# nRF_touch.net
KiCad netlist of a schematic drawn in EAGLE
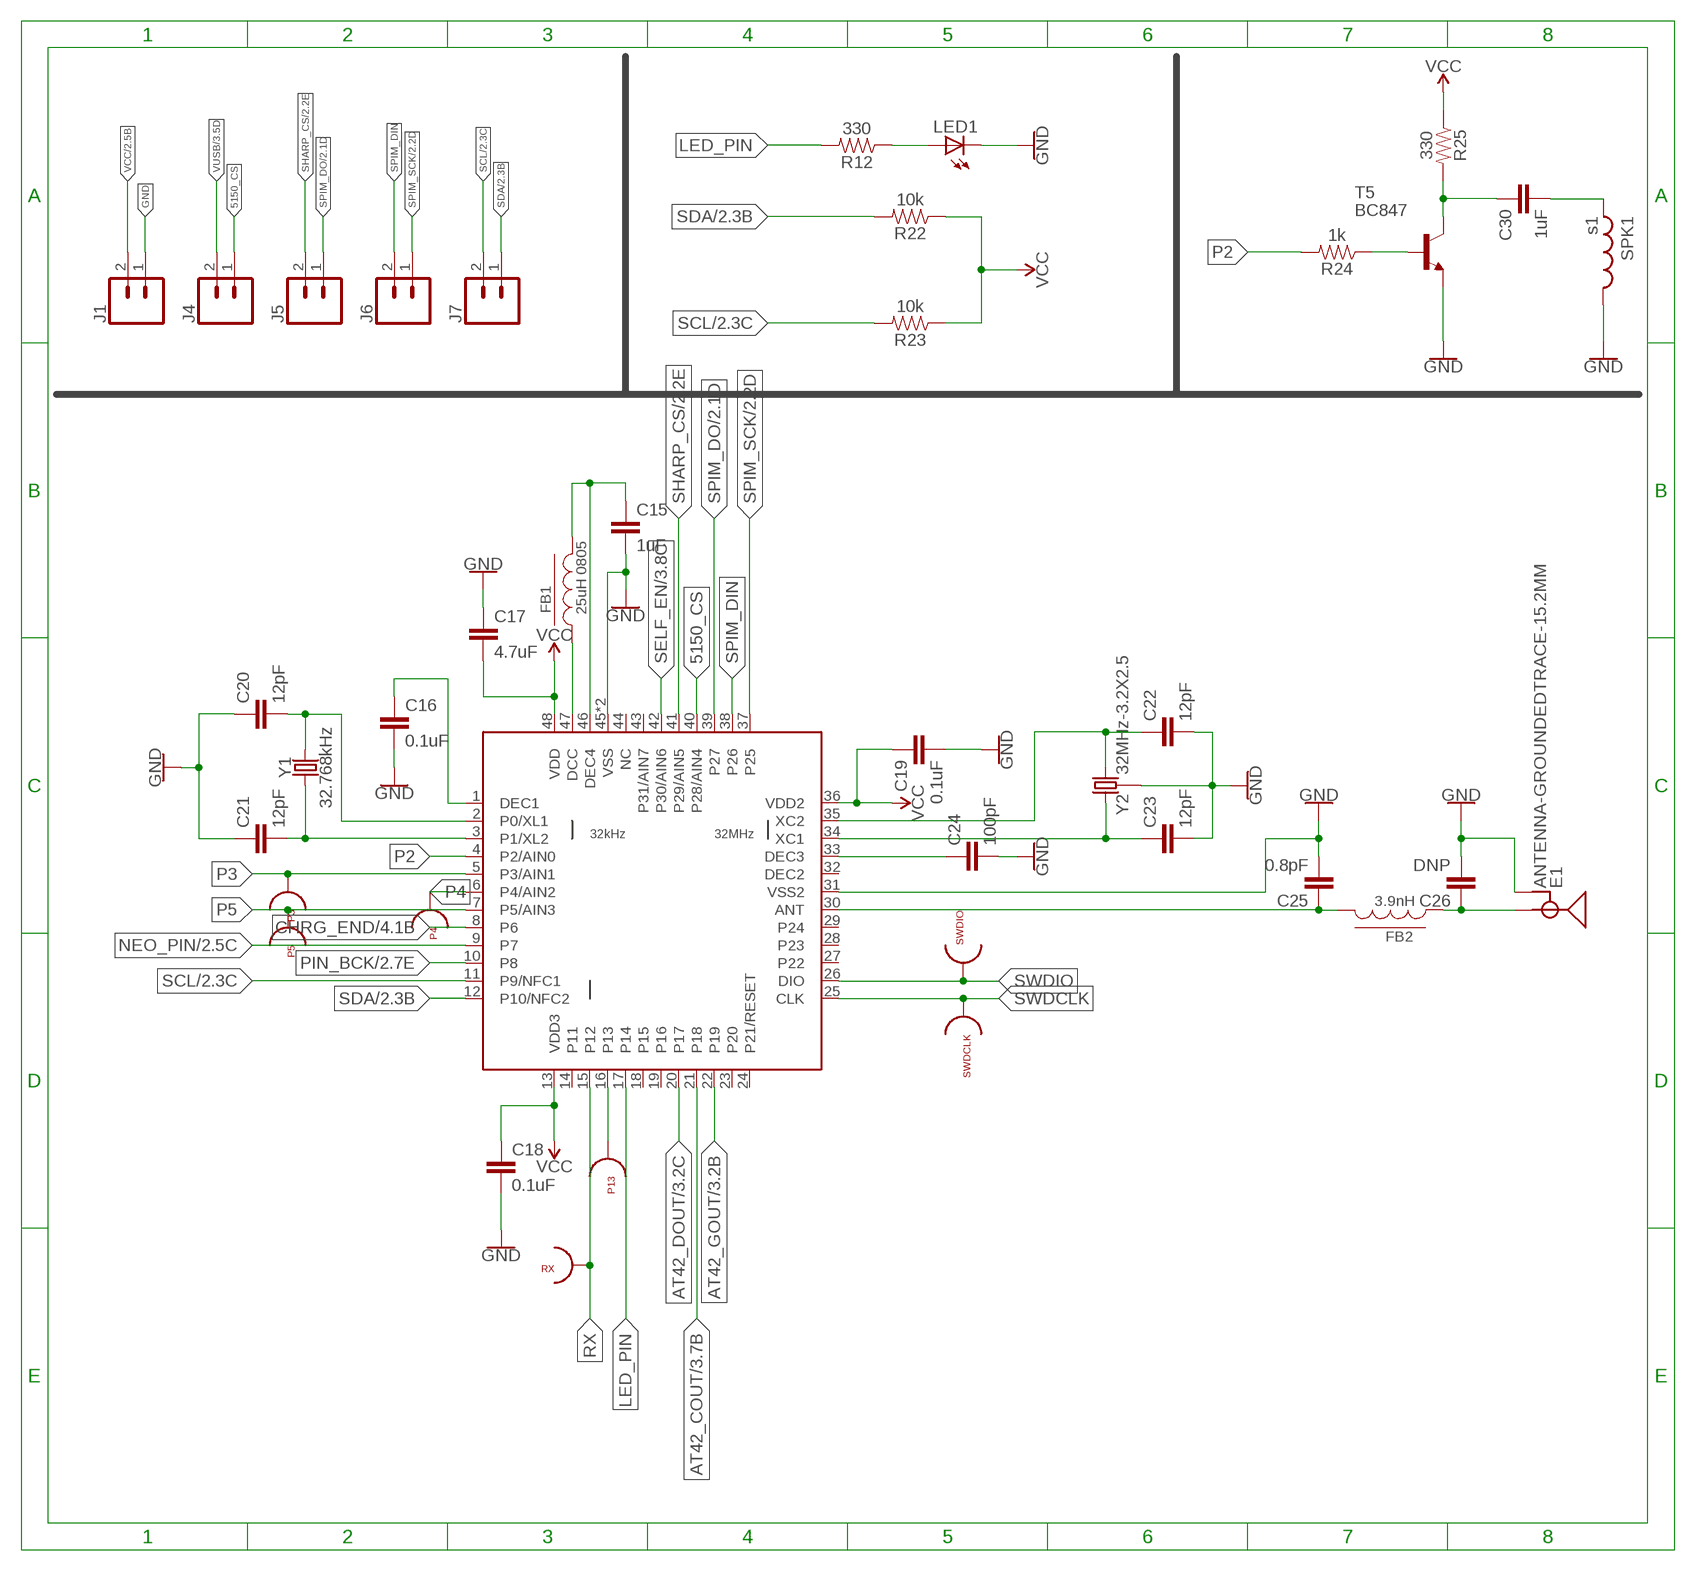
[diagram p0: schematic, sheet 1]
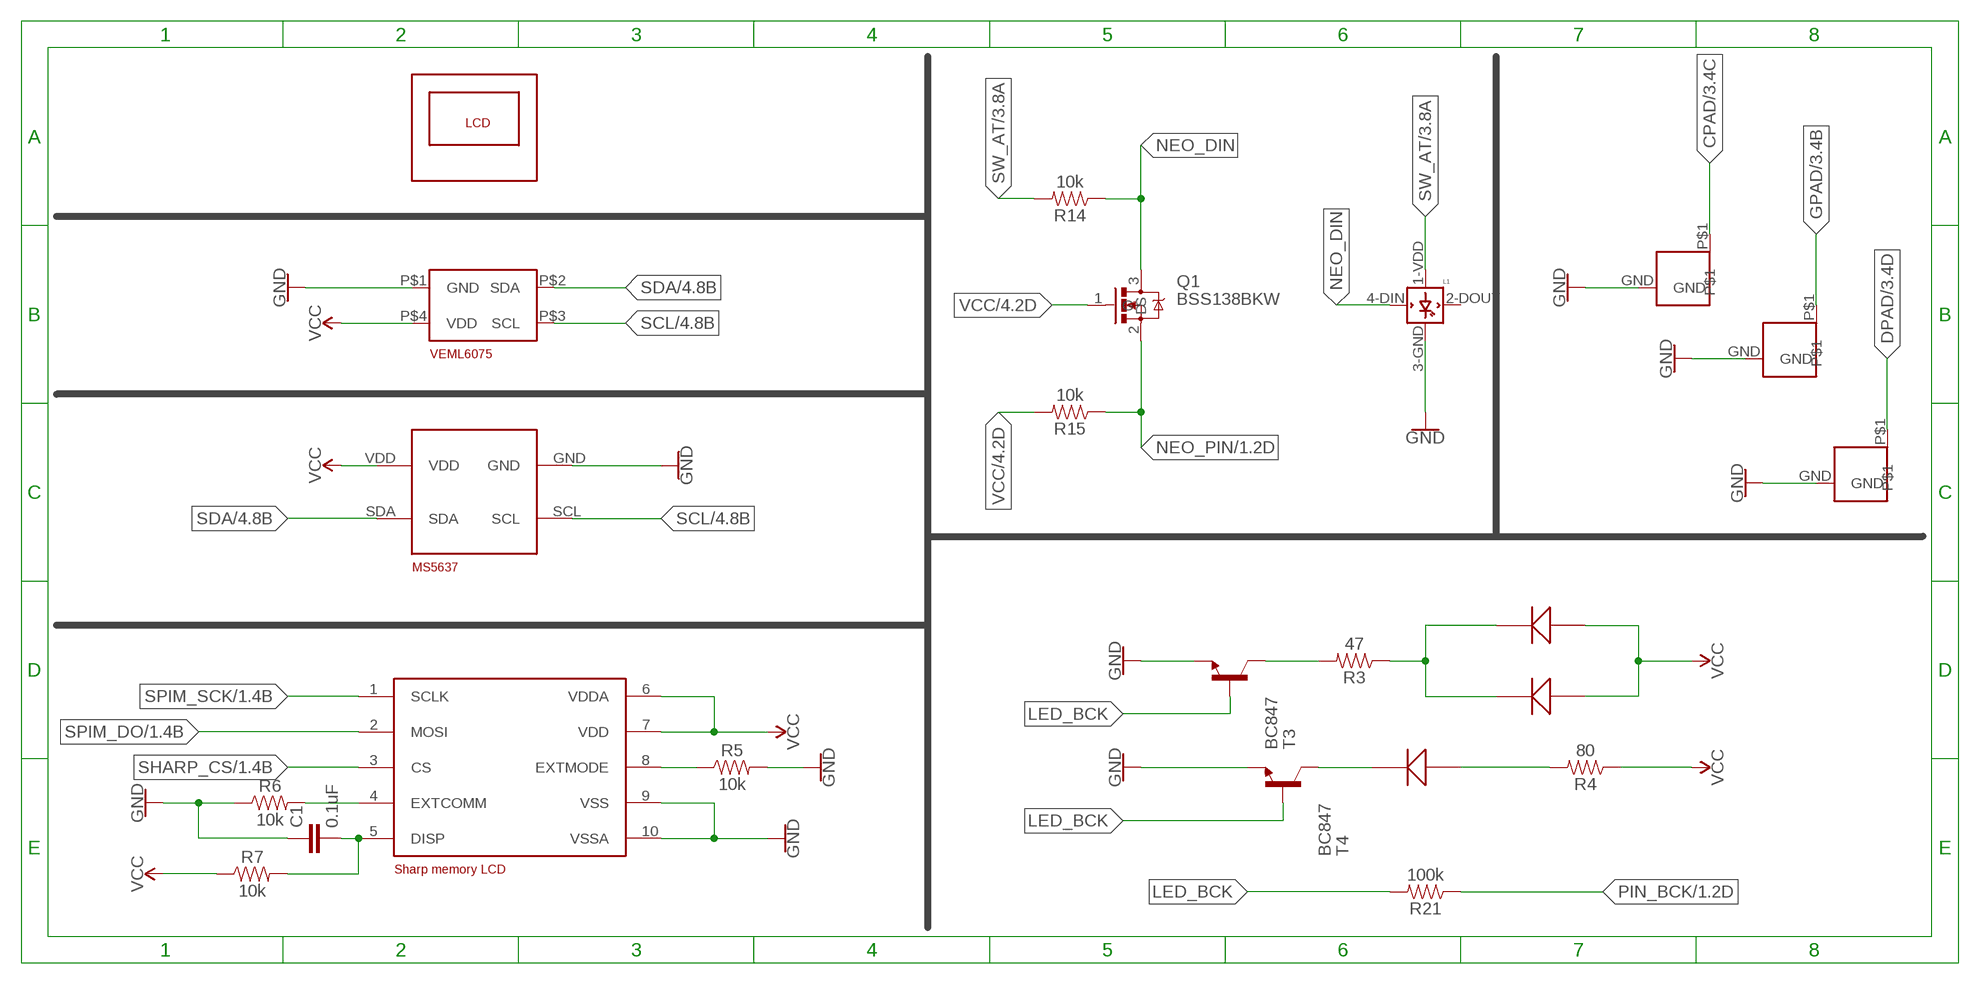
[diagram p1: schematic, sheet 2]
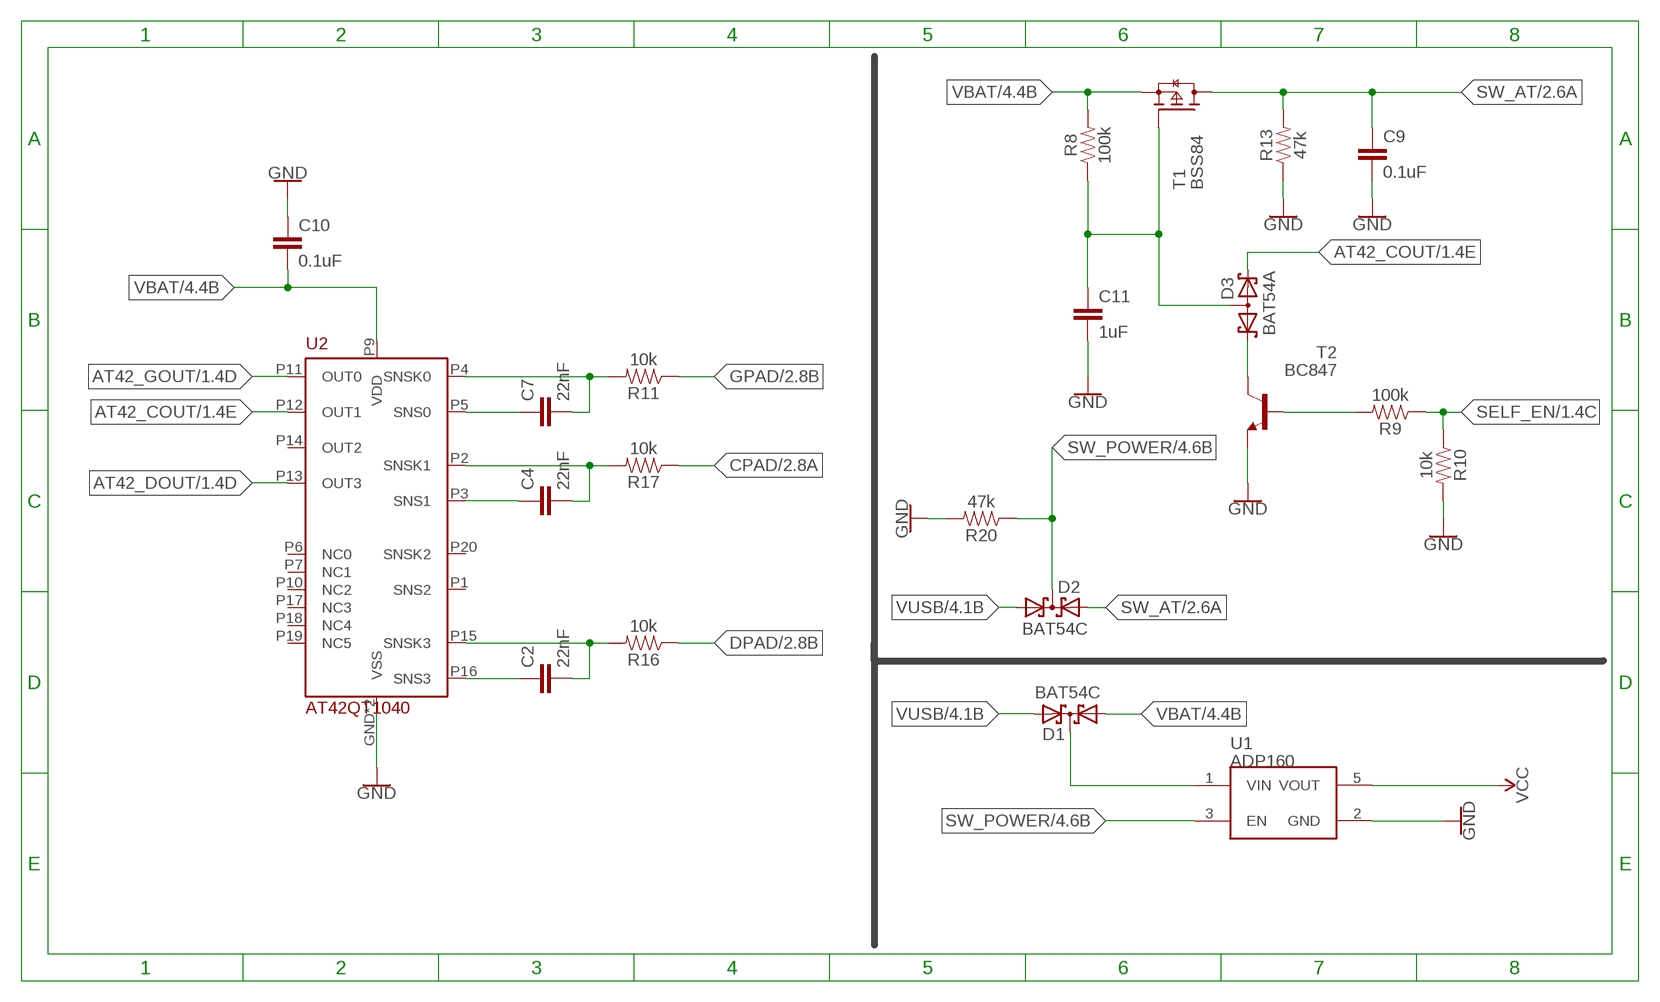
[diagram p2: schematic, sheet 3]
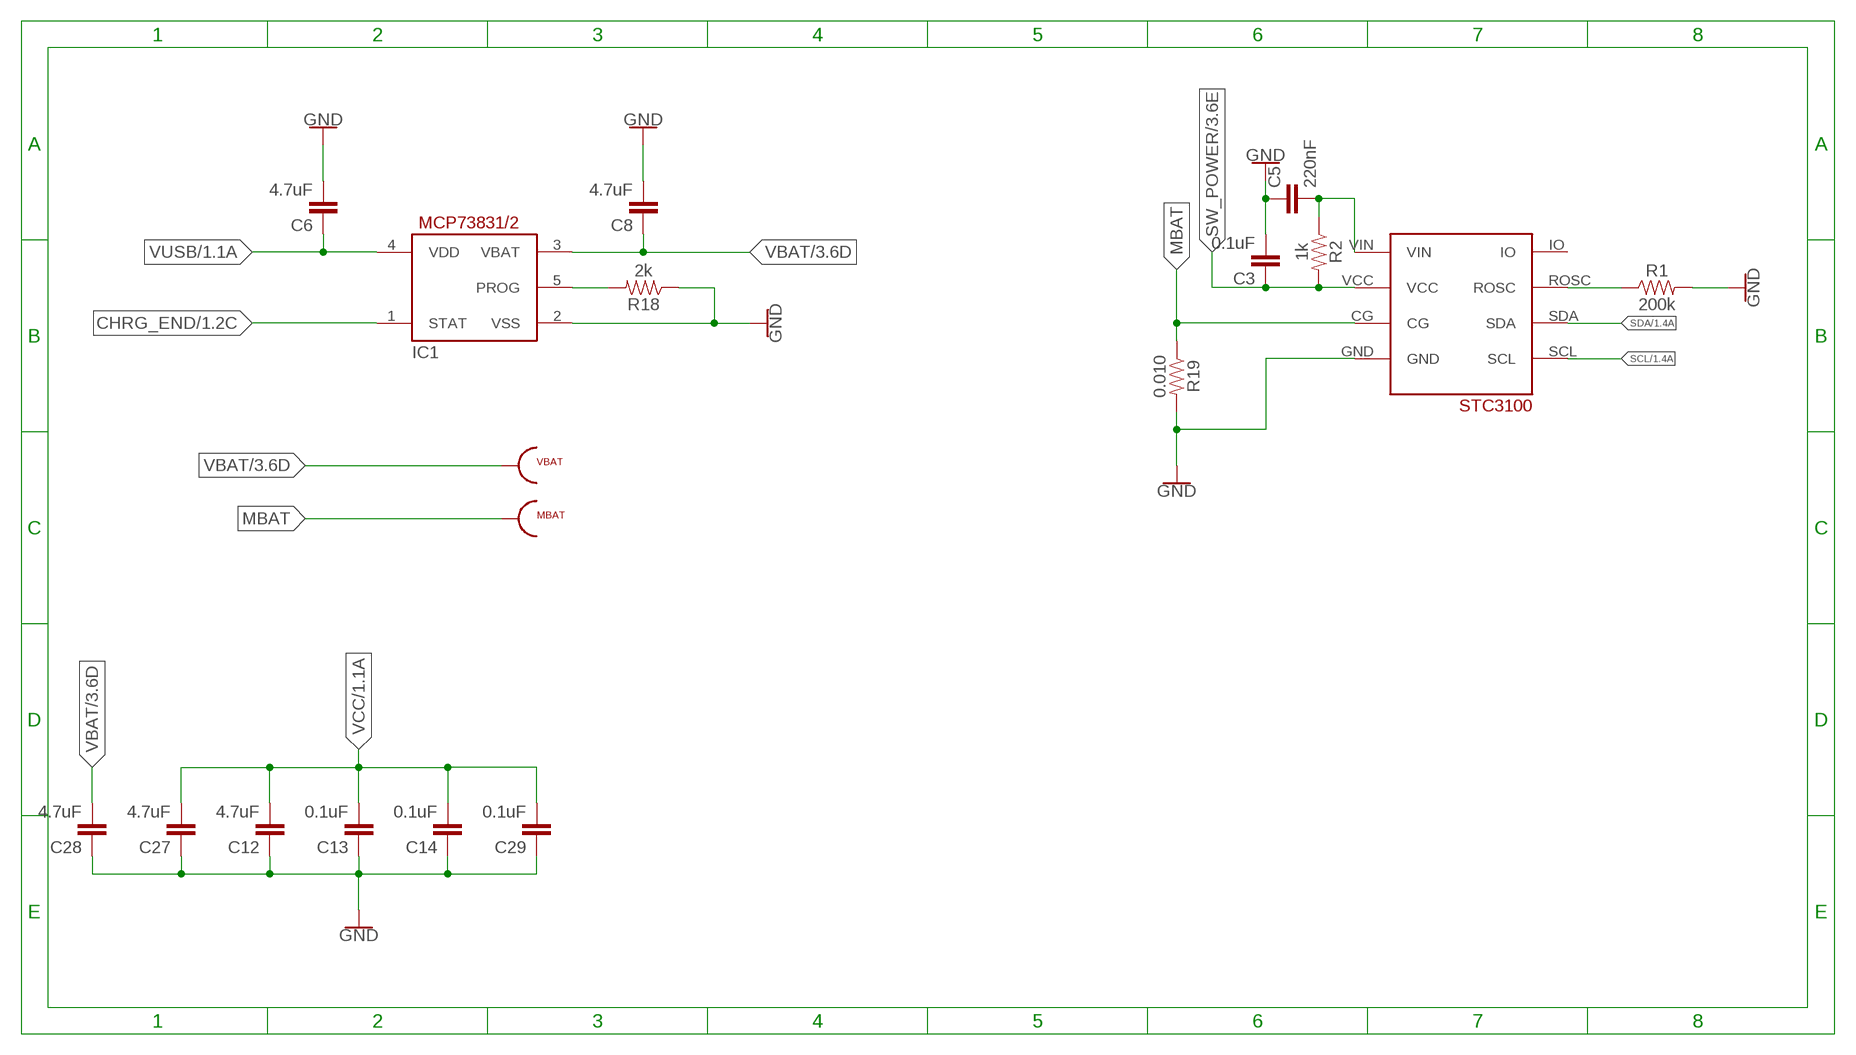
[diagram p3: schematic, sheet 4]

(export (version "E")
  (design (tool "Eeschema 10.0.6"))
  (components
    (comp (ref "C1")
      (value "0.1uF")
      (footprint "eagle-import:0603")
      (libsource (lib "eagle-import") (part "0.1UF-0603-25V-(+80/-20%)"))
    )
    (comp (ref "L1")
      (value "WS2812B")
      (footprint "eagle-import:WS2812B")
      (libsource (lib "eagle-import") (part "WS2812B"))
    )
    (comp (ref "MS5637")
      (value "MS5637")
      (footprint "eagle-import:MS5637")
      (libsource (lib "eagle-import") (part "MS5637"))
    )
    (comp (ref "Q1")
      (value "BSS138BKW")
      (footprint "eagle-import:SOT65P210X110-3N")
      (libsource (lib "eagle-import") (part "BSS138BKW"))
    )
    (comp (ref "R3")
      (value "47")
      (footprint "eagle-import:0603")
      (libsource (lib "eagle-import") (part "4.7KOHM-0603-1/10W-1%"))
    )
    (comp (ref "R4")
      (value "80")
      (footprint "eagle-import:0603")
      (libsource (lib "eagle-import") (part "4.7KOHM-0603-1/10W-1%"))
    )
    (comp (ref "R5")
      (value "10k")
      (footprint "eagle-import:0603")
      (libsource (lib "eagle-import") (part "4.7KOHM-0603-1/10W-1%"))
    )
    (comp (ref "R6")
      (value "10k")
      (footprint "eagle-import:0603")
      (libsource (lib "eagle-import") (part "4.7KOHM-0603-1/10W-1%"))
    )
    (comp (ref "R7")
      (value "10k")
      (footprint "eagle-import:0603")
      (libsource (lib "eagle-import") (part "4.7KOHM-0603-1/10W-1%"))
    )
    (comp (ref "R14")
      (value "10k")
      (footprint "eagle-import:0603")
      (libsource (lib "eagle-import") (part "4.7KOHM-0603-1/10W-1%"))
    )
    (comp (ref "R15")
      (value "10k")
      (footprint "eagle-import:0603")
      (libsource (lib "eagle-import") (part "4.7KOHM-0603-1/10W-1%"))
    )
    (comp (ref "R21")
      (value "100k")
      (footprint "eagle-import:0603")
      (libsource (lib "eagle-import") (part "4.7KOHM-0603-1/10W-1%"))
    )
    (comp (ref "S1")
      (value "L_BUTTON")
      (footprint "eagle-import:BUTTON")
      (libsource (lib "eagle-import") (part "BUTTON"))
    )
    (comp (ref "S2")
      (value "BUTTON")
      (footprint "eagle-import:BUTTON")
      (libsource (lib "eagle-import") (part "BUTTON"))
    )
    (comp (ref "S3")
      (value "L_BUTTON")
      (footprint "eagle-import:BUTTON")
      (libsource (lib "eagle-import") (part "BUTTON"))
    )
    (comp (ref "T3")
      (value "BC847")
      (footprint "eagle-import:SOT23")
      (libsource (lib "eagle-import") (part "BC847"))
    )
    (comp (ref "T4")
      (value "BC847")
      (footprint "eagle-import:SOT23")
      (libsource (lib "eagle-import") (part "BC847"))
    )
    (comp (ref "U$1")
      (value "KPA-2106SECK")
      (footprint "eagle-import:KPA-2106SECK")
      (libsource (lib "eagle-import") (part "KPA-2106SECK"))
    )
    (comp (ref "U$2")
      (value "VEML6075")
      (footprint "eagle-import:VEML6075")
      (libsource (lib "eagle-import") (part "VEML6075"))
    )
    (comp (ref "U$4")
      (value "SHARP27")
      (footprint "eagle-import:SHARP27")
      (libsource (lib "eagle-import") (part "SHARP27"))
    )
    (comp (ref "U$5")
      (value "SHARP27_FOOTPRINT")
      (footprint "eagle-import:LCD27")
      (libsource (lib "eagle-import") (part "SHARP27_FOOTPRINT"))
    )
    (comp (ref "U$7")
      (value "KPA-2106SECK")
      (footprint "eagle-import:KPA-2106SECK")
      (libsource (lib "eagle-import") (part "KPA-2106SECK"))
    )
    (comp (ref "U$8")
      (value "KPA-2106SECK")
      (footprint "eagle-import:KPA-2106SECK")
      (libsource (lib "eagle-import") (part "KPA-2106SECK"))
    )
    (comp (ref "C3")
      (value "0.1uF")
      (footprint "eagle-import:0603")
      (libsource (lib "eagle-import") (part "0.1UF-0603-25V-(+80/-20%)"))
    )
    (comp (ref "C5")
      (value "220nF")
      (footprint "eagle-import:0603")
      (libsource (lib "eagle-import") (part "0.1UF-0603-25V-(+80/-20%)"))
    )
    (comp (ref "C6")
      (value "4.7uF")
      (footprint "eagle-import:0603")
      (libsource (lib "eagle-import") (part "0.1UF-0603-25V-(+80/-20%)"))
    )
    (comp (ref "C8")
      (value "4.7uF")
      (footprint "eagle-import:0603")
      (libsource (lib "eagle-import") (part "0.1UF-0603-25V-(+80/-20%)"))
    )
    (comp (ref "C12")
      (value "4.7uF")
      (footprint "eagle-import:0603")
      (libsource (lib "eagle-import") (part "0.1UF-0603-25V-(+80/-20%)"))
    )
    (comp (ref "C13")
      (value "0.1uF")
      (footprint "eagle-import:0603")
      (libsource (lib "eagle-import") (part "0.1UF-0603-25V-(+80/-20%)"))
    )
    (comp (ref "C14")
      (value "0.1uF")
      (footprint "eagle-import:0603")
      (libsource (lib "eagle-import") (part "0.1UF-0603-25V-(+80/-20%)"))
    )
    (comp (ref "C27")
      (value "4.7uF")
      (footprint "eagle-import:0603")
      (libsource (lib "eagle-import") (part "0.1UF-0603-25V-(+80/-20%)"))
    )
    (comp (ref "C28")
      (value "4.7uF")
      (footprint "eagle-import:0603")
      (libsource (lib "eagle-import") (part "0.1UF-0603-25V-(+80/-20%)"))
    )
    (comp (ref "C29")
      (value "0.1uF")
      (footprint "eagle-import:0603")
      (libsource (lib "eagle-import") (part "0.1UF-0603-25V-(+80/-20%)"))
    )
    (comp (ref "IC1")
      (value "MCP73831/OT")
      (footprint "eagle-import:SOT23-5L")
      (libsource (lib "eagle-import") (part "MCP73831/OT"))
    )
    (comp (ref "MBAT")
      (value "TESTPOINT_22")
      (footprint "eagle-import:TESTPOINT_22")
      (libsource (lib "eagle-import") (part "TESTPOINT_22"))
    )
    (comp (ref "R1")
      (value "200k")
      (footprint "eagle-import:0603")
      (libsource (lib "eagle-import") (part "4.7KOHM-0603-1/10W-1%"))
    )
    (comp (ref "R2")
      (value "1k")
      (footprint "eagle-import:0603")
      (libsource (lib "eagle-import") (part "4.7KOHM-0603-1/10W-1%"))
    )
    (comp (ref "R18")
      (value "2k")
      (footprint "eagle-import:0603")
      (libsource (lib "eagle-import") (part "4.7KOHM-0603-1/10W-1%"))
    )
    (comp (ref "R19")
      (value "0.010")
      (footprint "eagle-import:0603")
      (libsource (lib "eagle-import") (part "4.7KOHM-0603-1/10W-1%"))
    )
    (comp (ref "U$3")
      (value "STC3100")
      (footprint "eagle-import:STC3100")
      (libsource (lib "eagle-import") (part "STC3100"))
    )
    (comp (ref "VBAT")
      (value "TESTPOINT_22")
      (footprint "eagle-import:TESTPOINT_22")
      (libsource (lib "eagle-import") (part "TESTPOINT_22"))
    )
    (comp (ref "C2")
      (value "22nF")
      (footprint "eagle-import:0603")
      (libsource (lib "eagle-import") (part "0.1UF-0603-25V-5%"))
    )
    (comp (ref "C4")
      (value "22nF")
      (footprint "eagle-import:0603")
      (libsource (lib "eagle-import") (part "0.1UF-0603-25V-5%"))
    )
    (comp (ref "C7")
      (value "22nF")
      (footprint "eagle-import:0603")
      (libsource (lib "eagle-import") (part "0.1UF-0603-25V-5%"))
    )
    (comp (ref "C9")
      (value "0.1uF")
      (footprint "eagle-import:0603")
      (libsource (lib "eagle-import") (part "0.1UF-0603-25V-5%"))
    )
    (comp (ref "C10")
      (value "0.1uF")
      (footprint "eagle-import:0603")
      (libsource (lib "eagle-import") (part "0.1UF-0603-25V-5%"))
    )
    (comp (ref "C11")
      (value "1uF")
      (footprint "eagle-import:0603")
      (libsource (lib "eagle-import") (part "0.1UF-0603-25V-5%"))
    )
    (comp (ref "D1")
      (value "BAT54C")
      (footprint "eagle-import:SOT23")
      (libsource (lib "eagle-import") (part "BAT754C"))
    )
    (comp (ref "D2")
      (value "BAT54C")
      (footprint "eagle-import:SOT23")
      (libsource (lib "eagle-import") (part "BAT754C"))
    )
    (comp (ref "D3")
      (value "BAT54A")
      (footprint "eagle-import:SOT23")
      (libsource (lib "eagle-import") (part "BAT754A"))
    )
    (comp (ref "R8")
      (value "100k")
      (footprint "eagle-import:0603")
      (libsource (lib "eagle-import") (part "4.7KOHM-0603-1/10W-1%"))
    )
    (comp (ref "R9")
      (value "100k")
      (footprint "eagle-import:0603")
      (libsource (lib "eagle-import") (part "4.7KOHM-0603-1/10W-1%"))
    )
    (comp (ref "R10")
      (value "10k")
      (footprint "eagle-import:0603")
      (libsource (lib "eagle-import") (part "4.7KOHM-0603-1/10W-1%"))
    )
    (comp (ref "R11")
      (value "10k")
      (footprint "eagle-import:0603")
      (libsource (lib "eagle-import") (part "4.7KOHM-0603-1/10W-1%"))
    )
    (comp (ref "R13")
      (value "47k")
      (footprint "eagle-import:0603")
      (libsource (lib "eagle-import") (part "4.7KOHM-0603-1/10W-1%"))
    )
    (comp (ref "R16")
      (value "10k")
      (footprint "eagle-import:0603")
      (libsource (lib "eagle-import") (part "4.7KOHM-0603-1/10W-1%"))
    )
    (comp (ref "R17")
      (value "10k")
      (footprint "eagle-import:0603")
      (libsource (lib "eagle-import") (part "4.7KOHM-0603-1/10W-1%"))
    )
    (comp (ref "R20")
      (value "47k")
      (footprint "eagle-import:0603")
      (libsource (lib "eagle-import") (part "4.7KOHM-0603-1/10W-1%"))
    )
    (comp (ref "T1")
      (value "BSS84")
      (footprint "eagle-import:SOT23")
      (libsource (lib "eagle-import") (part "BSS84"))
    )
    (comp (ref "T2")
      (value "BC847")
      (footprint "eagle-import:SOT23")
      (libsource (lib "eagle-import") (part "BC847"))
    )
    (comp (ref "U1")
      (value "ADP160")
      (footprint "eagle-import:SOT23-5")
      (libsource (lib "eagle-import") (part "ADP160"))
    )
    (comp (ref "U2")
      (value "AT42QT1040")
      (footprint "eagle-import:VQFN20")
      (libsource (lib "eagle-import") (part "AT42QT1040"))
    )
    (comp (ref "C15")
      (value "1uF")
      (footprint "eagle-import:0603")
      (libsource (lib "eagle-import") (part "4.7UF0603"))
    )
    (comp (ref "C16")
      (value "0.1uF")
      (footprint "eagle-import:0603")
      (libsource (lib "eagle-import") (part "4.7UF0603"))
    )
    (comp (ref "C17")
      (value "4.7uF")
      (footprint "eagle-import:0603")
      (libsource (lib "eagle-import") (part "4.7UF0603"))
    )
    (comp (ref "C18")
      (value "0.1uF")
      (footprint "eagle-import:0603")
      (libsource (lib "eagle-import") (part "4.7UF0603"))
    )
    (comp (ref "C19")
      (value "0.1uF")
      (footprint "eagle-import:0603")
      (libsource (lib "eagle-import") (part "4.7UF0603"))
    )
    (comp (ref "C20")
      (value "12pF")
      (footprint "eagle-import:0603")
      (libsource (lib "eagle-import") (part "4.7UF0603"))
    )
    (comp (ref "C21")
      (value "12pF")
      (footprint "eagle-import:0603")
      (libsource (lib "eagle-import") (part "4.7UF0603"))
    )
    (comp (ref "C22")
      (value "12pF")
      (footprint "eagle-import:0603")
      (libsource (lib "eagle-import") (part "4.7UF0603"))
    )
    (comp (ref "C23")
      (value "12pF")
      (footprint "eagle-import:0603")
      (libsource (lib "eagle-import") (part "4.7UF0603"))
    )
    (comp (ref "C24")
      (value "100pF")
      (footprint "eagle-import:0603")
      (libsource (lib "eagle-import") (part "4.7UF0603"))
    )
    (comp (ref "C25")
      (value "0.8pF")
      (footprint "eagle-import:0603")
      (libsource (lib "eagle-import") (part "4.7UF0603"))
    )
    (comp (ref "C26")
      (value "DNP")
      (footprint "eagle-import:0603")
      (libsource (lib "eagle-import") (part "4.7UF0603"))
    )
    (comp (ref "C30")
      (value "1uF")
      (footprint "eagle-import:0603")
      (libsource (lib "eagle-import") (part "4.7UF0603"))
    )
    (comp (ref "E1")
      (value "ANTENNA-GROUNDEDTRACE-15.2MM")
      (footprint "eagle-import:TRACE_ANTENNA_2.4GHZ_15.2MM")
      (libsource (lib "eagle-import") (part "ANTENNA-GROUNDEDTRACE-15.2MM"))
    )
    (comp (ref "FB1")
      (value "25uH 0805")
      (footprint "eagle-import:L0805")
      (libsource (lib "eagle-import") (part "FB_0805"))
    )
    (comp (ref "FB2")
      (value "3.9nH")
      (footprint "eagle-import:L0805")
      (libsource (lib "eagle-import") (part "FB_0805"))
    )
    (comp (ref "J1")
      (value "CONN_02")
      (footprint "eagle-import:1X02")
      (libsource (lib "eagle-import") (part "CONN_02"))
    )
    (comp (ref "J4")
      (value "CONN_02")
      (footprint "eagle-import:1X02")
      (libsource (lib "eagle-import") (part "CONN_02"))
    )
    (comp (ref "J5")
      (value "CONN_02")
      (footprint "eagle-import:1X02")
      (libsource (lib "eagle-import") (part "CONN_02"))
    )
    (comp (ref "J6")
      (value "CONN_02")
      (footprint "eagle-import:1X02")
      (libsource (lib "eagle-import") (part "CONN_02"))
    )
    (comp (ref "J7")
      (value "CONN_02")
      (footprint "eagle-import:1X02")
      (libsource (lib "eagle-import") (part "CONN_02"))
    )
    (comp (ref "LED1")
      (value "LEDCHIPLED_1206")
      (footprint "eagle-import:CHIPLED_1206")
      (libsource (lib "eagle-import") (part "LEDCHIPLED_1206"))
    )
    (comp (ref "P3")
      (value "p3")
      (footprint "eagle-import:TESTPOINT_22")
      (libsource (lib "eagle-import") (part "TESTPOINT_22"))
    )
    (comp (ref "P4")
      (value "TESTPOINT_22")
      (footprint "eagle-import:TESTPOINT_22")
      (libsource (lib "eagle-import") (part "TESTPOINT_22"))
    )
    (comp (ref "P5")
      (value "TESTPOINT_22")
      (footprint "eagle-import:TESTPOINT_22")
      (libsource (lib "eagle-import") (part "TESTPOINT_22"))
    )
    (comp (ref "P13")
      (value "TESTPOINT_22")
      (footprint "eagle-import:TESTPOINT_22")
      (libsource (lib "eagle-import") (part "TESTPOINT_22"))
    )
    (comp (ref "R12")
      (value "330")
      (footprint "eagle-import:0603")
      (libsource (lib "eagle-import") (part "4.7KOHM-0603-1/10W-1%"))
    )
    (comp (ref "R22")
      (value "10k")
      (footprint "eagle-import:0603")
      (libsource (lib "eagle-import") (part "4.7KOHM-0603-1/10W-1%"))
    )
    (comp (ref "R23")
      (value "10k")
      (footprint "eagle-import:0603")
      (libsource (lib "eagle-import") (part "4.7KOHM-0603-1/10W-1%"))
    )
    (comp (ref "R24")
      (value "1k")
      (footprint "eagle-import:0603")
      (libsource (lib "eagle-import") (part "4.7KOHM-0603-1/10W-1%"))
    )
    (comp (ref "R25")
      (value "330")
      (footprint "eagle-import:0603")
      (libsource (lib "eagle-import") (part "4.7KOHM-0603-1/10W-1%"))
    )
    (comp (ref "RX")
      (value "TESTPOINT_22")
      (footprint "eagle-import:TESTPOINT_22")
      (libsource (lib "eagle-import") (part "TESTPOINT_22"))
    )
    (comp (ref "SPK1")
      (value "s1")
      (footprint "eagle-import:IND-2020")
      (libsource (lib "eagle-import") (part "MDMK2020T4R7MM"))
    )
    (comp (ref "SWDCLK")
      (value "TESTPOINT_22")
      (footprint "eagle-import:TESTPOINT_22")
      (libsource (lib "eagle-import") (part "TESTPOINT_22"))
    )
    (comp (ref "SWDIO")
      (value "TESTPOINT_22")
      (footprint "eagle-import:TESTPOINT_22")
      (libsource (lib "eagle-import") (part "TESTPOINT_22"))
    )
    (comp (ref "T5")
      (value "BC847")
      (footprint "eagle-import:SOT23")
      (libsource (lib "eagle-import") (part "BC847"))
    )
    (comp (ref "U$6")
      (value "NRF52832NRF52832-QFAA")
      (footprint "eagle-import:QFN48")
      (libsource (lib "eagle-import") (part "NRF52832NRF52832-QFAA"))
    )
    (comp (ref "Y1")
      (value "32.768kHz")
      (footprint "eagle-import:CRYSTAL-SMD-3.2X1.5MM")
      (libsource (lib "eagle-import") (part "CRYSTAL-32.768KHZSMD-3.2X1.5"))
    )
    (comp (ref "Y2")
      (value "32MHz-3.2X2.5")
      (footprint "eagle-import:CRYSTAL-SMD-5X3.2-4PAD")
      (libsource (lib "eagle-import") (part "CRYSTAL-GROUNDEDSMD-5X3.2"))
    )
  )
  (nets
    (net (code "1") (name "5150_CS") (class "Default")
      (node (ref "J4") (pin "1") (pinfunction "1_1") (pintype "passive"))
      (node (ref "U$6") (pin "40") (pinfunction "P28/AIN4_40") (pintype "bidirectional"))
    )
    (net (code "2") (name "AT42_COUT") (class "Default")
      (node (ref "D3") (pin "2") (pinfunction "K2_2") (pintype "passive"))
      (node (ref "U$6") (pin "21") (pinfunction "P18_21") (pintype "bidirectional"))
      (node (ref "U2") (pin "P12") (pinfunction "OUT1_P12") (pintype "bidirectional"))
    )
    (net (code "3") (name "AT42_DOUT") (class "Default")
      (node (ref "U$6") (pin "20") (pinfunction "P17_20") (pintype "bidirectional"))
      (node (ref "U2") (pin "P13") (pinfunction "OUT3_P13") (pintype "bidirectional"))
    )
    (net (code "4") (name "AT42_GOUT") (class "Default")
      (node (ref "U$6") (pin "22") (pinfunction "P19_22") (pintype "bidirectional"))
      (node (ref "U2") (pin "P11") (pinfunction "OUT0_P11") (pintype "bidirectional"))
    )
    (net (code "5") (name "CHRG_END") (class "Default")
      (node (ref "IC1") (pin "1") (pinfunction "STAT_1") (pintype "output"))
      (node (ref "U$6") (pin "8") (pinfunction "P6_8") (pintype "bidirectional"))
    )
    (net (code "6") (name "CPAD") (class "Default")
      (node (ref "R17") (pin "1") (pinfunction "1_1") (pintype "passive"))
      (node (ref "S2") (pin "P$1") (pinfunction "P$1_P$1") (pintype "bidirectional"))
    )
    (net (code "7") (name "DPAD") (class "Default")
      (node (ref "R16") (pin "1") (pinfunction "1_1") (pintype "passive"))
      (node (ref "S1") (pin "P$1") (pinfunction "P$1_P$1") (pintype "bidirectional"))
    )
    (net (code "8") (name "GND") (class "Default")
      (node (ref "C1") (pin "1") (pinfunction "1_1") (pintype "passive"))
      (node (ref "C10") (pin "1") (pinfunction "1_1") (pintype "passive"))
      (node (ref "C11") (pin "2") (pinfunction "2_2") (pintype "passive"))
      (node (ref "C12") (pin "1") (pinfunction "1_1") (pintype "passive"))
      (node (ref "C13") (pin "1") (pinfunction "1_1") (pintype "passive"))
      (node (ref "C14") (pin "1") (pinfunction "1_1") (pintype "passive"))
      (node (ref "C15") (pin "2") (pinfunction "2_2") (pintype "passive"))
      (node (ref "C16") (pin "2") (pinfunction "2_2") (pintype "passive"))
      (node (ref "C17") (pin "1") (pinfunction "1_1") (pintype "passive"))
      (node (ref "C18") (pin "2") (pinfunction "2_2") (pintype "passive"))
      (node (ref "C19") (pin "2") (pinfunction "2_2") (pintype "passive"))
      (node (ref "C20") (pin "1") (pinfunction "1_1") (pintype "passive"))
      (node (ref "C21") (pin "1") (pinfunction "1_1") (pintype "passive"))
      (node (ref "C22") (pin "2") (pinfunction "2_2") (pintype "passive"))
      (node (ref "C23") (pin "2") (pinfunction "2_2") (pintype "passive"))
      (node (ref "C24") (pin "2") (pinfunction "2_2") (pintype "passive"))
      (node (ref "C25") (pin "2") (pinfunction "2_2") (pintype "passive"))
      (node (ref "C26") (pin "2") (pinfunction "2_2") (pintype "passive"))
      (node (ref "C27") (pin "1") (pinfunction "1_1") (pintype "passive"))
      (node (ref "C28") (pin "1") (pinfunction "1_1") (pintype "passive"))
      (node (ref "C29") (pin "1") (pinfunction "1_1") (pintype "passive"))
      (node (ref "C3") (pin "2") (pinfunction "2_2") (pintype "passive"))
      (node (ref "C5") (pin "1") (pinfunction "1_1") (pintype "passive"))
      (node (ref "C6") (pin "2") (pinfunction "2_2") (pintype "passive"))
      (node (ref "C8") (pin "2") (pinfunction "2_2") (pintype "passive"))
      (node (ref "C9") (pin "2") (pinfunction "2_2") (pintype "passive"))
      (node (ref "E1") (pin "GND") (pinfunction "GND_GND") (pintype "bidirectional"))
      (node (ref "IC1") (pin "2") (pinfunction "VSS_2") (pintype "power_in"))
      (node (ref "J1") (pin "1") (pinfunction "1_1") (pintype "passive"))
      (node (ref "L1") (pin "3-GND") (pinfunction "GND_3-GND") (pintype "bidirectional"))
      (node (ref "LED1") (pin "C") (pinfunction "C_C") (pintype "passive"))
      (node (ref "MS5637") (pin "GND") (pinfunction "GND_GND") (pintype "bidirectional"))
      (node (ref "R1") (pin "2") (pinfunction "2_2") (pintype "passive"))
      (node (ref "R10") (pin "2") (pinfunction "2_2") (pintype "passive"))
      (node (ref "R13") (pin "1") (pinfunction "1_1") (pintype "passive"))
      (node (ref "R18") (pin "1") (pinfunction "1_1") (pintype "passive"))
      (node (ref "R19") (pin "2") (pinfunction "2_2") (pintype "passive"))
      (node (ref "R20") (pin "2") (pinfunction "2_2") (pintype "passive"))
      (node (ref "R5") (pin "2") (pinfunction "2_2") (pintype "passive"))
      (node (ref "R6") (pin "1") (pinfunction "1_1") (pintype "passive"))
      (node (ref "S1") (pin "GND") (pinfunction "GND_GND") (pintype "bidirectional"))
      (node (ref "S2") (pin "GND") (pinfunction "GND_GND") (pintype "bidirectional"))
      (node (ref "S3") (pin "GND") (pinfunction "GND_GND") (pintype "bidirectional"))
      (node (ref "SPK1") (pin "P$2") (pinfunction "2_P$2") (pintype "passive"))
      (node (ref "T2") (pin "2") (pinfunction "E_2") (pintype "passive"))
      (node (ref "T3") (pin "2") (pinfunction "E_2") (pintype "passive"))
      (node (ref "T4") (pin "2") (pinfunction "E_2") (pintype "passive"))
      (node (ref "T5") (pin "2") (pinfunction "E_2") (pintype "passive"))
      (node (ref "U$2") (pin "P$1") (pinfunction "GND_P$1") (pintype "bidirectional"))
      (node (ref "U$3") (pin "GND") (pinfunction "GND_GND") (pintype "bidirectional"))
      (node (ref "U$4") (pin "10") (pinfunction "VSSA_10") (pintype "bidirectional"))
      (node (ref "U$4") (pin "9") (pinfunction "VSS_9") (pintype "bidirectional"))
      (node (ref "U$6") (pin "31") (pinfunction "VSS2_31") (pintype "bidirectional"))
      (node (ref "U$6") (pin "45") (pinfunction "VSS_45") (pintype "bidirectional"))
      (node (ref "U$6") (pin "GND") (pinfunction "VSS_GND") (pintype "bidirectional"))
      (node (ref "U1") (pin "2") (pinfunction "GND_2") (pintype "bidirectional"))
      (node (ref "U2") (pin "GND") (pinfunction "VSS_GND") (pintype "power_in"))
      (node (ref "U2") (pin "P8") (pinfunction "VSS_P8") (pintype "power_in"))
      (node (ref "Y2") (pin "2") (pinfunction "3_2") (pintype "passive"))
      (node (ref "Y2") (pin "4") (pinfunction "3_4") (pintype "passive"))
    )
    (net (code "9") (name "GPAD") (class "Default")
      (node (ref "R11") (pin "1") (pinfunction "1_1") (pintype "passive"))
      (node (ref "S3") (pin "P$1") (pinfunction "P$1_P$1") (pintype "bidirectional"))
    )
    (net (code "10") (name "LED_BCK") (class "Default")
      (node (ref "R21") (pin "2") (pinfunction "2_2") (pintype "passive"))
      (node (ref "T3") (pin "1") (pinfunction "B_1") (pintype "passive"))
      (node (ref "T4") (pin "1") (pinfunction "B_1") (pintype "passive"))
    )
    (net (code "11") (name "LED_PIN") (class "Default")
      (node (ref "R12") (pin "2") (pinfunction "2_2") (pintype "passive"))
      (node (ref "U$6") (pin "17") (pinfunction "P14_17") (pintype "bidirectional"))
    )
    (net (code "12") (name "MBAT") (class "Default")
      (node (ref "MBAT") (pin "P$1") (pinfunction "P$1_P$1") (pintype "bidirectional"))
      (node (ref "R19") (pin "1") (pinfunction "1_1") (pintype "passive"))
      (node (ref "U$3") (pin "CG") (pinfunction "CG_CG") (pintype "bidirectional"))
    )
    (net (code "13") (name "NEO_DIN") (class "Default")
      (node (ref "L1") (pin "4-DIN") (pinfunction "DIN_4-DIN") (pintype "input"))
      (node (ref "Q1") (pin "3") (pinfunction "D_3") (pintype "passive"))
      (node (ref "R14") (pin "1") (pinfunction "1_1") (pintype "passive"))
    )
    (net (code "14") (name "NEO_PIN") (class "Default")
      (node (ref "Q1") (pin "2") (pinfunction "S_2") (pintype "passive"))
      (node (ref "R15") (pin "1") (pinfunction "1_1") (pintype "passive"))
      (node (ref "U$6") (pin "9") (pinfunction "P7_9") (pintype "bidirectional"))
    )
    (net (code "15") (name "Net-(C5-Pad2)") (class "Default")
      (node (ref "C5") (pin "2") (pinfunction "2_2") (pintype "passive"))
      (node (ref "R2") (pin "1") (pinfunction "1_1") (pintype "passive"))
      (node (ref "U$3") (pin "VIN") (pinfunction "VIN_VIN") (pintype "bidirectional"))
    )
    (net (code "16") (name "Net-(D1-K1K2)") (class "Default")
      (node (ref "D1") (pin "3") (pinfunction "K1K2_3") (pintype "passive"))
      (node (ref "U1") (pin "1") (pinfunction "VIN_1") (pintype "bidirectional"))
    )
    (net (code "17") (name "Net-(D3-A1A2)") (class "Default")
      (node (ref "C11") (pin "1") (pinfunction "1_1") (pintype "passive"))
      (node (ref "D3") (pin "3") (pinfunction "A1A2_3") (pintype "passive"))
      (node (ref "R8") (pin "1") (pinfunction "1_1") (pintype "passive"))
      (node (ref "T1") (pin "1") (pinfunction "G_1") (pintype "passive"))
    )
    (net (code "18") (name "Net-(D3-K1)") (class "Default")
      (node (ref "D3") (pin "1") (pinfunction "K1_1") (pintype "passive"))
      (node (ref "T2") (pin "3") (pinfunction "C_3") (pintype "passive"))
    )
    (net (code "19") (name "Net-(E1-SIGNAL)") (class "Default")
      (node (ref "C26") (pin "1") (pinfunction "1_1") (pintype "passive"))
      (node (ref "E1") (pin "ANT") (pinfunction "SIGNAL_ANT") (pintype "bidirectional"))
      (node (ref "FB2") (pin "1") (pinfunction "1_1") (pintype "passive"))
    )
    (net (code "20") (name "Net-(IC1-PROG)") (class "Default")
      (node (ref "IC1") (pin "5") (pinfunction "PROG_5") (pintype "input"))
      (node (ref "R18") (pin "2") (pinfunction "2_2") (pintype "passive"))
    )
    (net (code "21") (name "Net-(LED1-PadA)") (class "Default")
      (node (ref "LED1") (pin "A") (pinfunction "A_A") (pintype "passive"))
      (node (ref "R12") (pin "1") (pinfunction "1_1") (pintype "passive"))
    )
    (net (code "22") (name "Net-(R1-Pad1)") (class "Default")
      (node (ref "R1") (pin "1") (pinfunction "1_1") (pintype "passive"))
      (node (ref "U$3") (pin "ROSC") (pinfunction "ROSC_ROSC") (pintype "bidirectional"))
    )
    (net (code "23") (name "Net-(R3-Pad1)") (class "Default")
      (node (ref "R3") (pin "1") (pinfunction "1_1") (pintype "passive"))
      (node (ref "U$1") (pin "P$1") (pinfunction "P$1_P$1") (pintype "bidirectional"))
      (node (ref "U$7") (pin "P$1") (pinfunction "P$1_P$1") (pintype "bidirectional"))
    )
    (net (code "24") (name "Net-(R4-Pad2)") (class "Default")
      (node (ref "R4") (pin "2") (pinfunction "2_2") (pintype "passive"))
      (node (ref "U$8") (pin "P$2") (pinfunction "P$2_P$2") (pintype "bidirectional"))
    )
    (net (code "25") (name "Net-(SPK1-1)") (class "Default")
      (node (ref "C30") (pin "2") (pinfunction "2_2") (pintype "passive"))
      (node (ref "SPK1") (pin "P$1") (pinfunction "1_P$1") (pintype "passive"))
    )
    (net (code "26") (name "Net-(T2-B)") (class "Default")
      (node (ref "R9") (pin "2") (pinfunction "2_2") (pintype "passive"))
      (node (ref "T2") (pin "1") (pinfunction "B_1") (pintype "passive"))
    )
    (net (code "27") (name "Net-(T3-C)") (class "Default")
      (node (ref "R3") (pin "2") (pinfunction "2_2") (pintype "passive"))
      (node (ref "T3") (pin "3") (pinfunction "C_3") (pintype "passive"))
    )
    (net (code "28") (name "Net-(T4-C)") (class "Default")
      (node (ref "T4") (pin "3") (pinfunction "C_3") (pintype "passive"))
      (node (ref "U$8") (pin "P$1") (pinfunction "P$1_P$1") (pintype "bidirectional"))
    )
    (net (code "29") (name "Net-(T5-B)") (class "Default")
      (node (ref "R24") (pin "1") (pinfunction "1_1") (pintype "passive"))
      (node (ref "T5") (pin "1") (pinfunction "B_1") (pintype "passive"))
    )
    (net (code "30") (name "Net-(T5-C)") (class "Default")
      (node (ref "C30") (pin "1") (pinfunction "1_1") (pintype "passive"))
      (node (ref "R25") (pin "2") (pinfunction "2_2") (pintype "passive"))
      (node (ref "T5") (pin "3") (pinfunction "C_3") (pintype "passive"))
    )
    (net (code "31") (name "Net-(U$4-DISP)") (class "Default")
      (node (ref "C1") (pin "2") (pinfunction "2_2") (pintype "passive"))
      (node (ref "R7") (pin "2") (pinfunction "2_2") (pintype "passive"))
      (node (ref "U$4") (pin "5") (pinfunction "DISP_5") (pintype "bidirectional"))
    )
    (net (code "32") (name "Net-(U$4-EXTCOMM)") (class "Default")
      (node (ref "R6") (pin "2") (pinfunction "2_2") (pintype "passive"))
      (node (ref "U$4") (pin "4") (pinfunction "EXTCOMM_4") (pintype "bidirectional"))
    )
    (net (code "33") (name "Net-(U$4-EXTMODE)") (class "Default")
      (node (ref "R5") (pin "1") (pinfunction "1_1") (pintype "passive"))
      (node (ref "U$4") (pin "8") (pinfunction "EXTMODE_8") (pintype "bidirectional"))
    )
    (net (code "34") (name "Net-(U$6-ANT)") (class "Default")
      (node (ref "C25") (pin "1") (pinfunction "1_1") (pintype "passive"))
      (node (ref "FB2") (pin "2") (pinfunction "2_2") (pintype "passive"))
      (node (ref "U$6") (pin "30") (pinfunction "ANT_30") (pintype "bidirectional"))
    )
    (net (code "35") (name "Net-(U$6-DCC)") (class "Default")
      (node (ref "FB1") (pin "1") (pinfunction "1_1") (pintype "passive"))
      (node (ref "U$6") (pin "47") (pinfunction "DCC_47") (pintype "bidirectional"))
    )
    (net (code "36") (name "Net-(U$6-DEC1)") (class "Default")
      (node (ref "C16") (pin "1") (pinfunction "1_1") (pintype "passive"))
      (node (ref "U$6") (pin "1") (pinfunction "DEC1_1") (pintype "bidirectional"))
    )
    (net (code "37") (name "Net-(U$6-DEC3)") (class "Default")
      (node (ref "C24") (pin "1") (pinfunction "1_1") (pintype "passive"))
      (node (ref "U$6") (pin "33") (pinfunction "DEC3_33") (pintype "bidirectional"))
    )
    (net (code "38") (name "Net-(U$6-DEC4)") (class "Default")
      (node (ref "C15") (pin "1") (pinfunction "1_1") (pintype "passive"))
      (node (ref "FB1") (pin "2") (pinfunction "2_2") (pintype "passive"))
      (node (ref "U$6") (pin "46") (pinfunction "DEC4_46") (pintype "bidirectional"))
    )
    (net (code "39") (name "Net-(U$6-P0{slash}XL1)") (class "Default")
      (node (ref "C20") (pin "2") (pinfunction "2_2") (pintype "passive"))
      (node (ref "U$6") (pin "2") (pinfunction "P0/XL1_2") (pintype "bidirectional"))
      (node (ref "Y1") (pin "P$2") (pinfunction "2_P$2") (pintype "passive"))
    )
    (net (code "40") (name "Net-(U$6-P1{slash}XL2)") (class "Default")
      (node (ref "C21") (pin "2") (pinfunction "2_2") (pintype "passive"))
      (node (ref "U$6") (pin "3") (pinfunction "P1/XL2_3") (pintype "bidirectional"))
      (node (ref "Y1") (pin "P$1") (pinfunction "1_P$1") (pintype "passive"))
    )
    (net (code "41") (name "Net-(U$6-P13)") (class "Default")
      (node (ref "P13") (pin "P$1") (pinfunction "P$1_P$1") (pintype "bidirectional"))
      (node (ref "U$6") (pin "16") (pinfunction "P13_16") (pintype "bidirectional"))
    )
    (net (code "42") (name "Net-(U$6-XC1)") (class "Default")
      (node (ref "C23") (pin "1") (pinfunction "1_1") (pintype "passive"))
      (node (ref "U$6") (pin "34") (pinfunction "XC1_34") (pintype "bidirectional"))
      (node (ref "Y2") (pin "3") (pinfunction "1_3") (pintype "passive"))
    )
    (net (code "43") (name "Net-(U$6-XC2)") (class "Default")
      (node (ref "C22") (pin "1") (pinfunction "1_1") (pintype "passive"))
      (node (ref "U$6") (pin "35") (pinfunction "XC2_35") (pintype "bidirectional"))
      (node (ref "Y2") (pin "1") (pinfunction "2_1") (pintype "passive"))
    )
    (net (code "44") (name "Net-(U2-SNS0)") (class "Default")
      (node (ref "C7") (pin "1") (pinfunction "1_1") (pintype "passive"))
      (node (ref "U2") (pin "P5") (pinfunction "SNS0_P5") (pintype "bidirectional"))
    )
    (net (code "45") (name "Net-(U2-SNS1)") (class "Default")
      (node (ref "C4") (pin "1") (pinfunction "1_1") (pintype "passive"))
      (node (ref "U2") (pin "P3") (pinfunction "SNS1_P3") (pintype "bidirectional"))
    )
    (net (code "46") (name "Net-(U2-SNS3)") (class "Default")
      (node (ref "C2") (pin "1") (pinfunction "1_1") (pintype "passive"))
      (node (ref "U2") (pin "P16") (pinfunction "SNS3_P16") (pintype "bidirectional"))
    )
    (net (code "47") (name "Net-(U2-SNSK0)") (class "Default")
      (node (ref "C7") (pin "2") (pinfunction "2_2") (pintype "passive"))
      (node (ref "R11") (pin "2") (pinfunction "2_2") (pintype "passive"))
      (node (ref "U2") (pin "P4") (pinfunction "SNSK0_P4") (pintype "bidirectional"))
    )
    (net (code "48") (name "Net-(U2-SNSK1)") (class "Default")
      (node (ref "C4") (pin "2") (pinfunction "2_2") (pintype "passive"))
      (node (ref "R17") (pin "2") (pinfunction "2_2") (pintype "passive"))
      (node (ref "U2") (pin "P2") (pinfunction "SNSK1_P2") (pintype "bidirectional"))
    )
    (net (code "49") (name "Net-(U2-SNSK3)") (class "Default")
      (node (ref "C2") (pin "2") (pinfunction "2_2") (pintype "passive"))
      (node (ref "R16") (pin "2") (pinfunction "2_2") (pintype "passive"))
      (node (ref "U2") (pin "P15") (pinfunction "SNSK3_P15") (pintype "bidirectional"))
    )
    (net (code "50") (name "P2") (class "Default")
      (node (ref "R24") (pin "2") (pinfunction "2_2") (pintype "passive"))
      (node (ref "U$6") (pin "4") (pinfunction "P2/AIN0_4") (pintype "bidirectional"))
    )
    (net (code "51") (name "P3") (class "Default")
      (node (ref "P3") (pin "P$1") (pinfunction "P$1_P$1") (pintype "bidirectional"))
      (node (ref "U$6") (pin "5") (pinfunction "P3/AIN1_5") (pintype "bidirectional"))
    )
    (net (code "52") (name "P4") (class "Default")
      (node (ref "P4") (pin "P$1") (pinfunction "P$1_P$1") (pintype "bidirectional"))
      (node (ref "U$6") (pin "6") (pinfunction "P4/AIN2_6") (pintype "bidirectional"))
    )
    (net (code "53") (name "P5") (class "Default")
      (node (ref "P5") (pin "P$1") (pinfunction "P$1_P$1") (pintype "bidirectional"))
      (node (ref "U$6") (pin "7") (pinfunction "P5/AIN3_7") (pintype "bidirectional"))
    )
    (net (code "54") (name "PIN_BCK") (class "Default")
      (node (ref "R21") (pin "1") (pinfunction "1_1") (pintype "passive"))
      (node (ref "U$6") (pin "10") (pinfunction "P8_10") (pintype "bidirectional"))
    )
    (net (code "55") (name "RX") (class "Default")
      (node (ref "RX") (pin "P$1") (pinfunction "P$1_P$1") (pintype "bidirectional"))
      (node (ref "U$6") (pin "15") (pinfunction "P12_15") (pintype "bidirectional"))
    )
    (net (code "56") (name "SCL") (class "Default")
      (node (ref "J7") (pin "2") (pinfunction "2_2") (pintype "passive"))
      (node (ref "MS5637") (pin "SCL") (pinfunction "SCL_SCL") (pintype "bidirectional"))
      (node (ref "R23") (pin "2") (pinfunction "2_2") (pintype "passive"))
      (node (ref "U$2") (pin "P$3") (pinfunction "SCL_P$3") (pintype "bidirectional"))
      (node (ref "U$3") (pin "SCL") (pinfunction "SCL_SCL") (pintype "bidirectional"))
      (node (ref "U$6") (pin "11") (pinfunction "P9/NFC1_11") (pintype "bidirectional"))
    )
    (net (code "57") (name "SDA") (class "Default")
      (node (ref "J7") (pin "1") (pinfunction "1_1") (pintype "passive"))
      (node (ref "MS5637") (pin "SDA") (pinfunction "SDA_SDA") (pintype "bidirectional"))
      (node (ref "R22") (pin "2") (pinfunction "2_2") (pintype "passive"))
      (node (ref "U$2") (pin "P$2") (pinfunction "SDA_P$2") (pintype "bidirectional"))
      (node (ref "U$3") (pin "SDA") (pinfunction "SDA_SDA") (pintype "bidirectional"))
      (node (ref "U$6") (pin "12") (pinfunction "P10/NFC2_12") (pintype "bidirectional"))
    )
    (net (code "58") (name "SELF_EN") (class "Default")
      (node (ref "R10") (pin "1") (pinfunction "1_1") (pintype "passive"))
      (node (ref "R9") (pin "1") (pinfunction "1_1") (pintype "passive"))
      (node (ref "U$6") (pin "42") (pinfunction "P30/AIN6_42") (pintype "bidirectional"))
    )
    (net (code "59") (name "SHARP_CS") (class "Default")
      (node (ref "J5") (pin "2") (pinfunction "2_2") (pintype "passive"))
      (node (ref "U$4") (pin "3") (pinfunction "CS_3") (pintype "bidirectional"))
      (node (ref "U$6") (pin "41") (pinfunction "P29/AIN5_41") (pintype "bidirectional"))
    )
    (net (code "60") (name "SPIM_DIN") (class "Default")
      (node (ref "J6") (pin "2") (pinfunction "2_2") (pintype "passive"))
      (node (ref "U$6") (pin "38") (pinfunction "P26_38") (pintype "bidirectional"))
    )
    (net (code "61") (name "SPIM_DO") (class "Default")
      (node (ref "J5") (pin "1") (pinfunction "1_1") (pintype "passive"))
      (node (ref "U$4") (pin "2") (pinfunction "MOSI_2") (pintype "bidirectional"))
      (node (ref "U$6") (pin "39") (pinfunction "P27_39") (pintype "bidirectional"))
    )
    (net (code "62") (name "SPIM_SCK") (class "Default")
      (node (ref "J6") (pin "1") (pinfunction "1_1") (pintype "passive"))
      (node (ref "U$4") (pin "1") (pinfunction "SCLK_1") (pintype "bidirectional"))
      (node (ref "U$6") (pin "37") (pinfunction "P25_37") (pintype "bidirectional"))
    )
    (net (code "63") (name "SWDCLK") (class "Default")
      (node (ref "SWDCLK") (pin "P$1") (pinfunction "P$1_P$1") (pintype "bidirectional"))
      (node (ref "U$6") (pin "25") (pinfunction "CLK_25") (pintype "bidirectional"))
    )
    (net (code "64") (name "SWDIO") (class "Default")
      (node (ref "SWDIO") (pin "P$1") (pinfunction "P$1_P$1") (pintype "bidirectional"))
      (node (ref "U$6") (pin "26") (pinfunction "DIO_26") (pintype "bidirectional"))
    )
    (net (code "65") (name "SW_AT") (class "Default")
      (node (ref "C9") (pin "1") (pinfunction "1_1") (pintype "passive"))
      (node (ref "D2") (pin "2") (pinfunction "A2_2") (pintype "passive"))
      (node (ref "L1") (pin "1-VDD") (pinfunction "VDD_1-VDD") (pintype "bidirectional"))
      (node (ref "R13") (pin "2") (pinfunction "2_2") (pintype "passive"))
      (node (ref "R14") (pin "2") (pinfunction "2_2") (pintype "passive"))
      (node (ref "T1") (pin "3") (pinfunction "D_3") (pintype "passive"))
    )
    (net (code "66") (name "SW_POWER") (class "Default")
      (node (ref "C3") (pin "1") (pinfunction "1_1") (pintype "passive"))
      (node (ref "D2") (pin "3") (pinfunction "K1K2_3") (pintype "passive"))
      (node (ref "R2") (pin "2") (pinfunction "2_2") (pintype "passive"))
      (node (ref "R20") (pin "1") (pinfunction "1_1") (pintype "passive"))
      (node (ref "U$3") (pin "VCC") (pinfunction "VCC_VCC") (pintype "bidirectional"))
      (node (ref "U1") (pin "3") (pinfunction "EN_3") (pintype "bidirectional"))
    )
    (net (code "67") (name "VBAT") (class "Default")
      (node (ref "C10") (pin "2") (pinfunction "2_2") (pintype "passive"))
      (node (ref "C28") (pin "2") (pinfunction "2_2") (pintype "passive"))
      (node (ref "C8") (pin "1") (pinfunction "1_1") (pintype "passive"))
      (node (ref "D1") (pin "1") (pinfunction "A1_1") (pintype "passive"))
      (node (ref "IC1") (pin "3") (pinfunction "VBAT_3") (pintype "bidirectional"))
      (node (ref "R8") (pin "2") (pinfunction "2_2") (pintype "passive"))
      (node (ref "T1") (pin "2") (pinfunction "S_2") (pintype "passive"))
      (node (ref "U2") (pin "P9") (pinfunction "VDD_P9") (pintype "power_in"))
      (node (ref "VBAT") (pin "P$1") (pinfunction "P$1_P$1") (pintype "bidirectional"))
    )
    (net (code "68") (name "VCC") (class "Default")
      (node (ref "C12") (pin "2") (pinfunction "2_2") (pintype "passive"))
      (node (ref "C13") (pin "2") (pinfunction "2_2") (pintype "passive"))
      (node (ref "C14") (pin "2") (pinfunction "2_2") (pintype "passive"))
      (node (ref "C17") (pin "2") (pinfunction "2_2") (pintype "passive"))
      (node (ref "C18") (pin "1") (pinfunction "1_1") (pintype "passive"))
      (node (ref "C19") (pin "1") (pinfunction "1_1") (pintype "passive"))
      (node (ref "C27") (pin "2") (pinfunction "2_2") (pintype "passive"))
      (node (ref "C29") (pin "2") (pinfunction "2_2") (pintype "passive"))
      (node (ref "J1") (pin "2") (pinfunction "2_2") (pintype "passive"))
      (node (ref "MS5637") (pin "VDD") (pinfunction "VDD_VDD") (pintype "bidirectional"))
      (node (ref "Q1") (pin "1") (pinfunction "G_1") (pintype "passive"))
      (node (ref "R15") (pin "2") (pinfunction "2_2") (pintype "passive"))
      (node (ref "R22") (pin "1") (pinfunction "1_1") (pintype "passive"))
      (node (ref "R23") (pin "1") (pinfunction "1_1") (pintype "passive"))
      (node (ref "R25") (pin "1") (pinfunction "1_1") (pintype "passive"))
      (node (ref "R4") (pin "1") (pinfunction "1_1") (pintype "passive"))
      (node (ref "R7") (pin "1") (pinfunction "1_1") (pintype "passive"))
      (node (ref "U$1") (pin "P$2") (pinfunction "P$2_P$2") (pintype "bidirectional"))
      (node (ref "U$2") (pin "P$4") (pinfunction "VDD_P$4") (pintype "bidirectional"))
      (node (ref "U$4") (pin "6") (pinfunction "VDDA_6") (pintype "bidirectional"))
      (node (ref "U$4") (pin "7") (pinfunction "VDD_7") (pintype "bidirectional"))
      (node (ref "U$6") (pin "13") (pinfunction "VDD3_13") (pintype "bidirectional"))
      (node (ref "U$6") (pin "36") (pinfunction "VDD2_36") (pintype "bidirectional"))
      (node (ref "U$6") (pin "48") (pinfunction "VDD_48") (pintype "bidirectional"))
      (node (ref "U$7") (pin "P$2") (pinfunction "P$2_P$2") (pintype "bidirectional"))
      (node (ref "U1") (pin "5") (pinfunction "VOUT_5") (pintype "bidirectional"))
    )
    (net (code "69") (name "VUSB") (class "Default")
      (node (ref "C6") (pin "1") (pinfunction "1_1") (pintype "passive"))
      (node (ref "D1") (pin "2") (pinfunction "A2_2") (pintype "passive"))
      (node (ref "D2") (pin "1") (pinfunction "A1_1") (pintype "passive"))
      (node (ref "IC1") (pin "4") (pinfunction "VDD_4") (pintype "power_in"))
      (node (ref "J4") (pin "2") (pinfunction "2_2") (pintype "passive"))
    )
    (net (code "70") (name "unconnected-(L1-DOUT-Pad2-DOUT)") (class "Default")
      (node (ref "L1") (pin "2-DOUT") (pinfunction "DOUT_2-DOUT") (pintype "output"))
    )
    (net (code "71") (name "unconnected-(U$3-PadIO)") (class "Default")
      (node (ref "U$3") (pin "IO") (pinfunction "IO_IO") (pintype "bidirectional"))
    )
    (net (code "72") (name "unconnected-(U$6-DEC2-Pad32)") (class "Default")
      (node (ref "U$6") (pin "32") (pinfunction "DEC2_32") (pintype "bidirectional"))
    )
    (net (code "73") (name "unconnected-(U$6-NC-Pad44)") (class "Default")
      (node (ref "U$6") (pin "44") (pinfunction "NC_44") (pintype "bidirectional"))
    )
    (net (code "74") (name "unconnected-(U$6-P11-Pad14)") (class "Default")
      (node (ref "U$6") (pin "14") (pinfunction "P11_14") (pintype "bidirectional"))
    )
    (net (code "75") (name "unconnected-(U$6-P15-Pad18)") (class "Default")
      (node (ref "U$6") (pin "18") (pinfunction "P15_18") (pintype "bidirectional"))
    )
    (net (code "76") (name "unconnected-(U$6-P16-Pad19)") (class "Default")
      (node (ref "U$6") (pin "19") (pinfunction "P16_19") (pintype "bidirectional"))
    )
    (net (code "77") (name "unconnected-(U$6-P20-Pad23)") (class "Default")
      (node (ref "U$6") (pin "23") (pinfunction "P20_23") (pintype "bidirectional"))
    )
    (net (code "78") (name "unconnected-(U$6-P21{slash}RESET-Pad24)") (class "Default")
      (node (ref "U$6") (pin "24") (pinfunction "P21/RESET_24") (pintype "bidirectional"))
    )
    (net (code "79") (name "unconnected-(U$6-P22-Pad27)") (class "Default")
      (node (ref "U$6") (pin "27") (pinfunction "P22_27") (pintype "bidirectional"))
    )
    (net (code "80") (name "unconnected-(U$6-P23-Pad28)") (class "Default")
      (node (ref "U$6") (pin "28") (pinfunction "P23_28") (pintype "bidirectional"))
    )
    (net (code "81") (name "unconnected-(U$6-P24-Pad29)") (class "Default")
      (node (ref "U$6") (pin "29") (pinfunction "P24_29") (pintype "bidirectional"))
    )
    (net (code "82") (name "unconnected-(U$6-P31{slash}AIN7-Pad43)") (class "Default")
      (node (ref "U$6") (pin "43") (pinfunction "P31/AIN7_43") (pintype "bidirectional"))
    )
    (net (code "83") (name "unconnected-(U2-NC0-PadP6)") (class "Default")
      (node (ref "U2") (pin "P6") (pinfunction "NC0_P6") (pintype "no_connect"))
    )
    (net (code "84") (name "unconnected-(U2-NC1-PadP7)") (class "Default")
      (node (ref "U2") (pin "P7") (pinfunction "NC1_P7") (pintype "no_connect"))
    )
    (net (code "85") (name "unconnected-(U2-NC2-PadP10)") (class "Default")
      (node (ref "U2") (pin "P10") (pinfunction "NC2_P10") (pintype "no_connect"))
    )
    (net (code "86") (name "unconnected-(U2-NC3-PadP17)") (class "Default")
      (node (ref "U2") (pin "P17") (pinfunction "NC3_P17") (pintype "no_connect"))
    )
    (net (code "87") (name "unconnected-(U2-NC4-PadP18)") (class "Default")
      (node (ref "U2") (pin "P18") (pinfunction "NC4_P18") (pintype "no_connect"))
    )
    (net (code "88") (name "unconnected-(U2-NC5-PadP19)") (class "Default")
      (node (ref "U2") (pin "P19") (pinfunction "NC5_P19") (pintype "no_connect"))
    )
    (net (code "89") (name "unconnected-(U2-OUT2-PadP14)") (class "Default")
      (node (ref "U2") (pin "P14") (pinfunction "OUT2_P14") (pintype "bidirectional"))
    )
    (net (code "90") (name "unconnected-(U2-SNS2-PadP1)") (class "Default")
      (node (ref "U2") (pin "P1") (pinfunction "SNS2_P1") (pintype "bidirectional"))
    )
    (net (code "91") (name "unconnected-(U2-SNSK2-PadP20)") (class "Default")
      (node (ref "U2") (pin "P20") (pinfunction "SNSK2_P20") (pintype "bidirectional"))
    )
  )
)
